# tinyDuinoCircuit.net
KiCad netlist of a schematic drawn in EAGLE
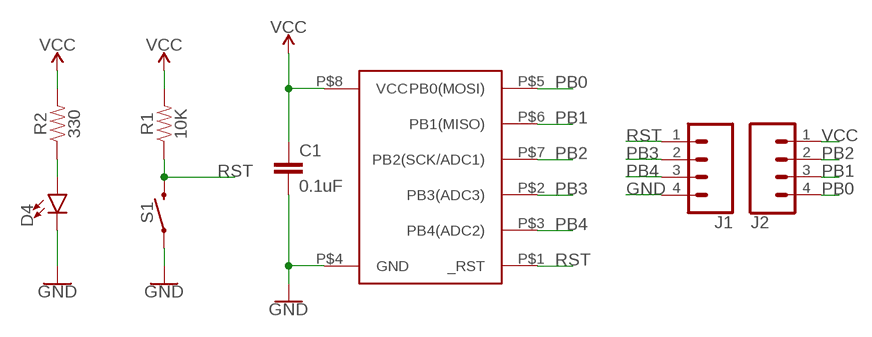
[diagram p0: schematic, sheet 1]

(export (version "E")
  (design (tool "Eeschema 10.0.6"))
  (components
    (comp (ref "C1")
      (value "0.1uF")
      (footprint "eagle-import:CAP-PTH-SMALL-KIT")
      (libsource (lib "eagle-import") (part "0.1UF-KIT-EZ-50V-20%"))
    )
    (comp (ref "D4")
      (value "LED-3MM-NO_SILK")
      (footprint "eagle-import:LED_3MM-NS")
      (libsource (lib "eagle-import") (part "LED-3MM-NO_SILK"))
    )
    (comp (ref "J1")
      (value "CONN_04")
      (footprint "eagle-import:1X04")
      (libsource (lib "eagle-import") (part "CONN_04"))
    )
    (comp (ref "J2")
      (value "CONN_04")
      (footprint "eagle-import:1X04")
      (libsource (lib "eagle-import") (part "CONN_04"))
    )
    (comp (ref "R1")
      (value "10K")
      (footprint "eagle-import:AXIAL-0.1")
      (libsource (lib "eagle-import") (part "1KOHM-VERT-1/4W-5%"))
    )
    (comp (ref "R2")
      (value "330")
      (footprint "eagle-import:AXIAL-0.1")
      (libsource (lib "eagle-import") (part "1KOHM-VERT-1/4W-5%"))
    )
    (comp (ref "S1")
      (value "MOMENTARY-SWITCH-SPST-PTH-6.0MM")
      (footprint "eagle-import:TACTILE_SWITCH_PTH_6.0MM")
      (libsource (lib "eagle-import") (part "MOMENTARY-SWITCH-SPST-PTH-6.0MM"))
    )
    (comp (ref "U$1")
      (value "ATTINY85-DIP8")
      (footprint "eagle-import:DIP8")
      (libsource (lib "eagle-import") (part "ATTINY85-DIP8"))
    )
  )
  (nets
    (net (code "1") (name "/PB0") (class "Default")
      (node (ref "J2") (pin "4") (pinfunction "4_4") (pintype "passive"))
      (node (ref "U$1") (pin "P$5") (pinfunction "PB0(MOSI)_P$5") (pintype "bidirectional"))
    )
    (net (code "2") (name "/PB1") (class "Default")
      (node (ref "J2") (pin "3") (pinfunction "3_3") (pintype "passive"))
      (node (ref "U$1") (pin "P$6") (pinfunction "PB1(MISO)_P$6") (pintype "bidirectional"))
    )
    (net (code "3") (name "/PB2") (class "Default")
      (node (ref "J2") (pin "2") (pinfunction "2_2") (pintype "passive"))
      (node (ref "U$1") (pin "P$7") (pinfunction "PB2(SCK/ADC1)_P$7") (pintype "bidirectional"))
    )
    (net (code "4") (name "/PB3") (class "Default")
      (node (ref "J1") (pin "2") (pinfunction "2_2") (pintype "passive"))
      (node (ref "U$1") (pin "P$2") (pinfunction "PB3(ADC3)_P$2") (pintype "bidirectional"))
    )
    (net (code "5") (name "/PB4") (class "Default")
      (node (ref "J1") (pin "3") (pinfunction "3_3") (pintype "passive"))
      (node (ref "U$1") (pin "P$3") (pinfunction "PB4(ADC2)_P$3") (pintype "bidirectional"))
    )
    (net (code "6") (name "/RST") (class "Default")
      (node (ref "J1") (pin "1") (pinfunction "1_1") (pintype "passive"))
      (node (ref "R1") (pin "P$1") (pinfunction "1_P$1") (pintype "passive"))
      (node (ref "S1") (pin "3") (pinfunction "2_3") (pintype "passive"))
      (node (ref "U$1") (pin "P$1") (pinfunction "_RST_P$1") (pintype "bidirectional"))
    )
    (net (code "7") (name "GND") (class "Default")
      (node (ref "C1") (pin "2") (pinfunction "2_2") (pintype "passive"))
      (node (ref "D4") (pin "K") (pinfunction "C_K") (pintype "passive"))
      (node (ref "J1") (pin "4") (pinfunction "4_4") (pintype "passive"))
      (node (ref "S1") (pin "1") (pinfunction "1_1") (pintype "passive"))
      (node (ref "U$1") (pin "P$4") (pinfunction "GND_P$4") (pintype "bidirectional"))
    )
    (net (code "8") (name "Net-(R2-1)") (class "Default")
      (node (ref "D4") (pin "A") (pinfunction "A_A") (pintype "passive"))
      (node (ref "R2") (pin "P$1") (pinfunction "1_P$1") (pintype "passive"))
    )
    (net (code "9") (name "VCC") (class "Default")
      (node (ref "C1") (pin "1") (pinfunction "1_1") (pintype "passive"))
      (node (ref "J2") (pin "1") (pinfunction "1_1") (pintype "passive"))
      (node (ref "R1") (pin "P$2") (pinfunction "2_P$2") (pintype "passive"))
      (node (ref "R2") (pin "P$2") (pinfunction "2_P$2") (pintype "passive"))
      (node (ref "U$1") (pin "P$8") (pinfunction "VCC_P$8") (pintype "bidirectional"))
    )
  )
)
